# digit.net
KiCad netlist of a schematic drawn in EAGLE
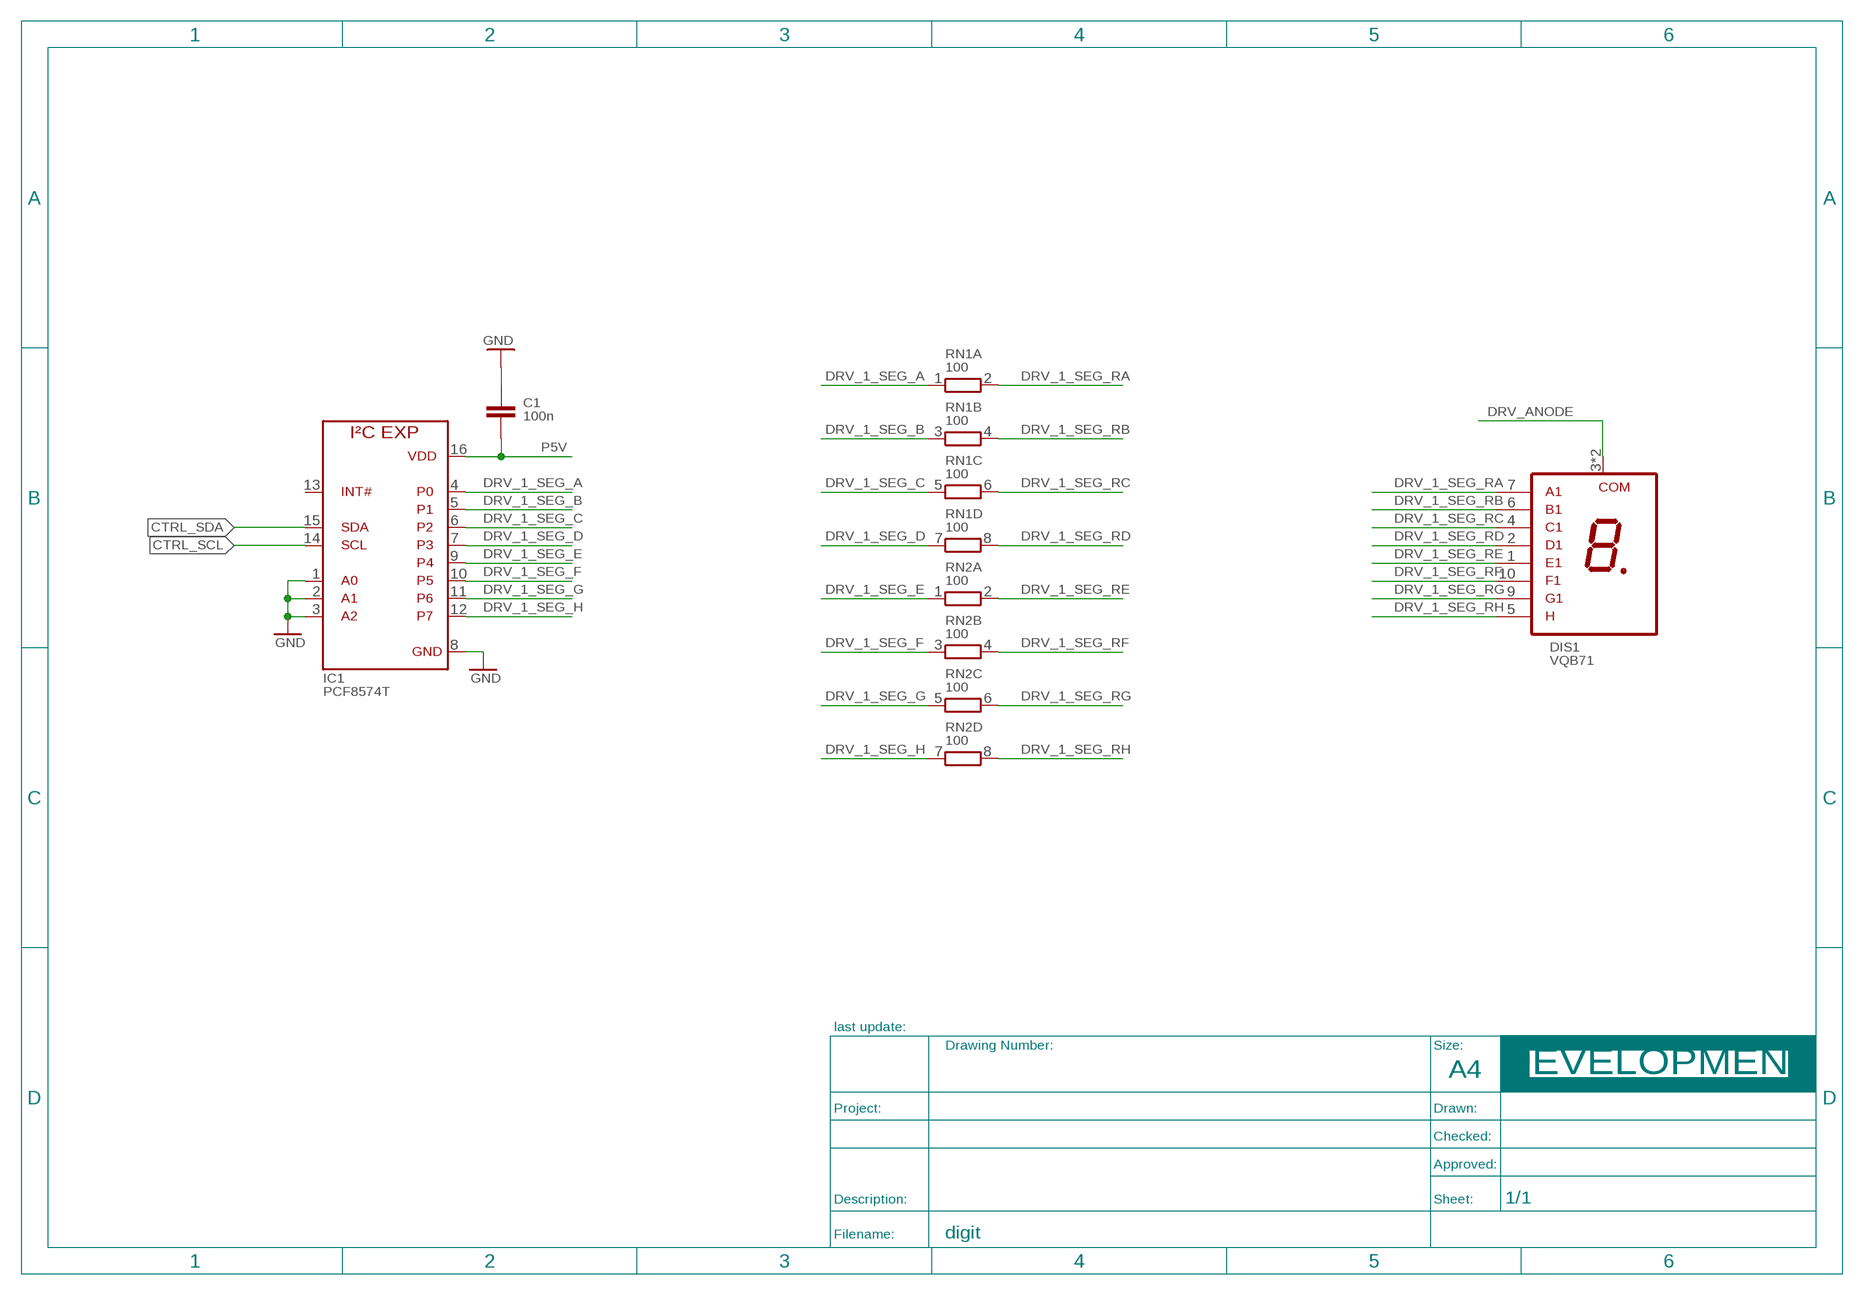
[diagram p0: schematic, sheet 1]

(export (version "E")
  (design (tool "Eeschema 10.0.6"))
  (components
    (comp (ref "C1")
      (value "100n")
      (footprint "eagle-import:S_0805")
      (fields (field (name "PART_CODE_BEL") "C_PAC_S_0805_VAL_100n"))
      (libsource (lib "eagle-import") (part "C_EU_S_0805"))
    )
    (comp (ref "DIS1")
      (value "VQB71")
      (footprint "eagle-import:T_VQB71")
      (libsource (lib "eagle-import") (part "VQB71"))
    )
    (comp (ref "IC1")
      (value "PCF8574T")
      (footprint "eagle-import:S_SOIC16")
      (libsource (lib "eagle-import") (part "PCF8574T"))
    )
    (comp (ref "RN1")
      (value "100")
      (footprint "eagle-import:T_SIL8")
      (fields (field (name "PART_CODE_BEL") "RN_PAC_T_SIL8_VAL_100"))
      (libsource (lib "eagle-import") (part "R_EU_ARRAY_4"))
    )
    (comp (ref "RN2")
      (value "100")
      (footprint "eagle-import:T_SIL8")
      (fields (field (name "PART_CODE_BEL") "RN_PAC_T_SIL8_VAL_100"))
      (libsource (lib "eagle-import") (part "R_EU_ARRAY_4"))
    )
  )
  (nets
    (net (code "1") (name "/DRV_1_SEG_A") (class "Default")
      (node (ref "IC1") (pin "4") (pinfunction "P0_4") (pintype "bidirectional"))
      (node (ref "RN1") (pin "1") (pinfunction "1_1") (pintype "passive"))
    )
    (net (code "2") (name "/DRV_1_SEG_B") (class "Default")
      (node (ref "IC1") (pin "5") (pinfunction "P1_5") (pintype "bidirectional"))
      (node (ref "RN1") (pin "3") (pinfunction "1_3") (pintype "passive"))
    )
    (net (code "3") (name "/DRV_1_SEG_C") (class "Default")
      (node (ref "IC1") (pin "6") (pinfunction "P2_6") (pintype "bidirectional"))
      (node (ref "RN1") (pin "5") (pinfunction "1_5") (pintype "passive"))
    )
    (net (code "4") (name "/DRV_1_SEG_D") (class "Default")
      (node (ref "IC1") (pin "7") (pinfunction "P3_7") (pintype "bidirectional"))
      (node (ref "RN1") (pin "7") (pinfunction "1_7") (pintype "passive"))
    )
    (net (code "5") (name "/DRV_1_SEG_E") (class "Default")
      (node (ref "IC1") (pin "9") (pinfunction "P4_9") (pintype "bidirectional"))
      (node (ref "RN2") (pin "1") (pinfunction "1_1") (pintype "passive"))
    )
    (net (code "6") (name "/DRV_1_SEG_F") (class "Default")
      (node (ref "IC1") (pin "10") (pinfunction "P5_10") (pintype "bidirectional"))
      (node (ref "RN2") (pin "3") (pinfunction "1_3") (pintype "passive"))
    )
    (net (code "7") (name "/DRV_1_SEG_G") (class "Default")
      (node (ref "IC1") (pin "11") (pinfunction "P6_11") (pintype "bidirectional"))
      (node (ref "RN2") (pin "5") (pinfunction "1_5") (pintype "passive"))
    )
    (net (code "8") (name "/DRV_1_SEG_H") (class "Default")
      (node (ref "IC1") (pin "12") (pinfunction "P7_12") (pintype "bidirectional"))
      (node (ref "RN2") (pin "7") (pinfunction "1_7") (pintype "passive"))
    )
    (net (code "9") (name "/DRV_1_SEG_RA") (class "Default")
      (node (ref "DIS1") (pin "7") (pinfunction "A1_7") (pintype "passive"))
      (node (ref "RN1") (pin "2") (pinfunction "2_2") (pintype "passive"))
    )
    (net (code "10") (name "/DRV_1_SEG_RB") (class "Default")
      (node (ref "DIS1") (pin "6") (pinfunction "B1_6") (pintype "passive"))
      (node (ref "RN1") (pin "4") (pinfunction "2_4") (pintype "passive"))
    )
    (net (code "11") (name "/DRV_1_SEG_RC") (class "Default")
      (node (ref "DIS1") (pin "4") (pinfunction "C1_4") (pintype "passive"))
      (node (ref "RN1") (pin "6") (pinfunction "2_6") (pintype "passive"))
    )
    (net (code "12") (name "/DRV_1_SEG_RD") (class "Default")
      (node (ref "DIS1") (pin "2") (pinfunction "D1_2") (pintype "passive"))
      (node (ref "RN1") (pin "8") (pinfunction "2_8") (pintype "passive"))
    )
    (net (code "13") (name "/DRV_1_SEG_RE") (class "Default")
      (node (ref "DIS1") (pin "1") (pinfunction "E1_1") (pintype "passive"))
      (node (ref "RN2") (pin "2") (pinfunction "2_2") (pintype "passive"))
    )
    (net (code "14") (name "/DRV_1_SEG_RF") (class "Default")
      (node (ref "DIS1") (pin "10") (pinfunction "F1_10") (pintype "passive"))
      (node (ref "RN2") (pin "4") (pinfunction "2_4") (pintype "passive"))
    )
    (net (code "15") (name "/DRV_1_SEG_RG") (class "Default")
      (node (ref "DIS1") (pin "9") (pinfunction "G1_9") (pintype "passive"))
      (node (ref "RN2") (pin "6") (pinfunction "2_6") (pintype "passive"))
    )
    (net (code "16") (name "/DRV_1_SEG_RH") (class "Default")
      (node (ref "DIS1") (pin "5") (pinfunction "DP1_5") (pintype "passive"))
      (node (ref "RN2") (pin "8") (pinfunction "2_8") (pintype "passive"))
    )
    (net (code "17") (name "/DRV_ANODE") (class "Default")
      (node (ref "DIS1") (pin "3") (pinfunction "COM1_3") (pintype "passive"))
      (node (ref "DIS1") (pin "8") (pinfunction "COM1_8") (pintype "passive"))
    )
    (net (code "18") (name "/P5V") (class "Default")
      (node (ref "C1") (pin "2") (pinfunction "2_2") (pintype "passive"))
      (node (ref "IC1") (pin "16") (pinfunction "VDD_16") (pintype "power_in"))
    )
    (net (code "19") (name "CTRL_SCL") (class "Default")
      (node (ref "IC1") (pin "14") (pinfunction "SCL_14") (pintype "input"))
    )
    (net (code "20") (name "CTRL_SDA") (class "Default")
      (node (ref "IC1") (pin "15") (pinfunction "SDA_15") (pintype "bidirectional"))
    )
    (net (code "21") (name "GND") (class "Default")
      (node (ref "C1") (pin "1") (pinfunction "1_1") (pintype "passive"))
      (node (ref "IC1") (pin "1") (pinfunction "A0_1") (pintype "input"))
      (node (ref "IC1") (pin "2") (pinfunction "A1_2") (pintype "input"))
      (node (ref "IC1") (pin "3") (pinfunction "A2_3") (pintype "input"))
      (node (ref "IC1") (pin "8") (pinfunction "GND_8") (pintype "power_in"))
    )
    (net (code "22") (name "unconnected-(IC1-~{INT}-Pad13)") (class "Default")
      (node (ref "IC1") (pin "13") (pinfunction "~{INT}_13") (pintype "output"))
    )
  )
)
